# Nucleo.net
KiCad netlist of a schematic drawn in Altium Designer
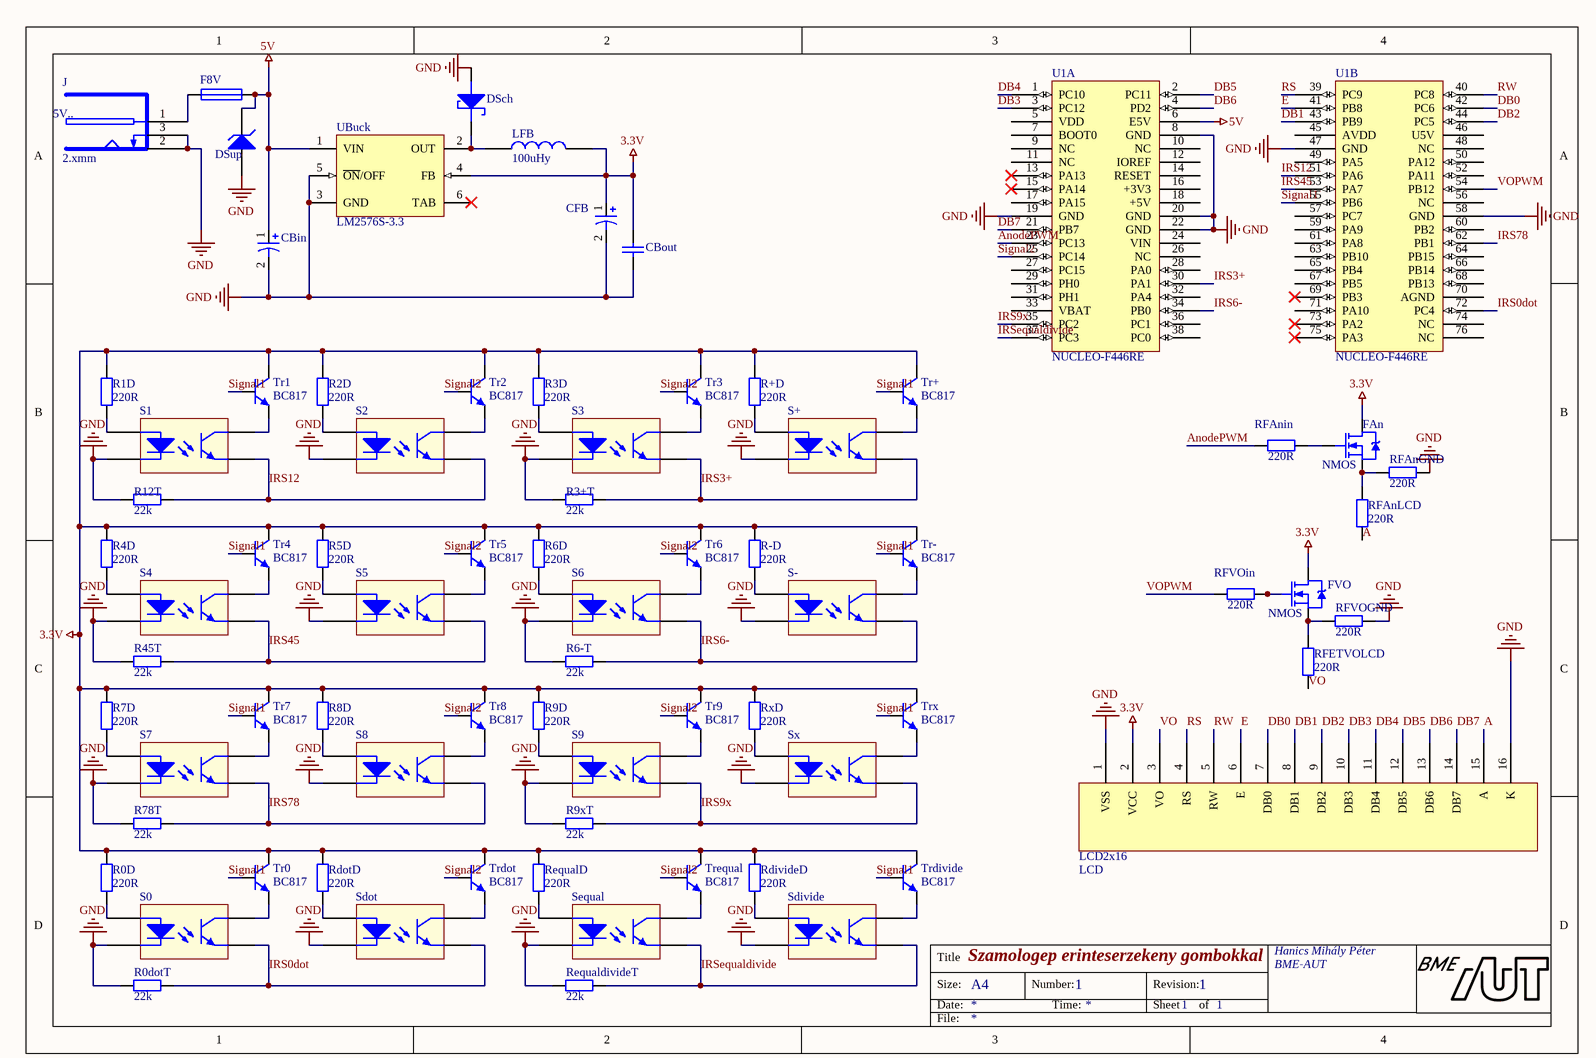
[diagram p0: Nucleo.SchDoc]

(export (version "E")
  (design (tool "Eeschema 10.0.6"))
  (components
    (comp (ref "CBin")
      (value "100uF")
      (footprint "CAP_100uF_ELKO")
      (description "100uF Capacitor")
      (fields (field (name "TOLERANCE") "20%") (field (name "VOLTAGE") "16V"))
      (libsource (lib "hallglib") (part "CAP100uF"))
    )
    (comp (ref "CBout")
      (value "100nF")
      (footprint "FP_0805_CAP_085")
      (description "Capacitor")
      (fields (field (name "TOLERANCE") "10%") (field (name "VOLTAGE") "50V"))
      (libsource (lib "hallglib") (part "CAP"))
    )
    (comp (ref "CFB")
      (value "1000uF")
      (footprint "CAP_Elko1000uF")
      (description "1000uF Capacitor")
      (fields (field (name "TOLERANCE") "20%") (field (name "VOLTAGE") "6.3V"))
      (libsource (lib "hallglib") (part "CAP1000uF"))
    )
    (comp (ref "DSch")
      (value "SCHOTTKY")
      (footprint "FP_SOD323-F")
      (description "Schottky diode")
      (libsource (lib "hallglib") (part "SCHOTTKY"))
    )
    (comp (ref "DSup")
      (value "~")
      (footprint "DiodeSMAJ5A")
      (description "Suppressor Diode")
      (libsource (lib "hallglib") (part "SMAJ5A"))
    )
    (comp (ref "F8V") (value "Fuse") (footprint "FP_MULTIFUSE") (libsource (lib "hallglib") (part "Fuse")))
    (comp (ref "FAn")
      (value "NMOS")
      (footprint "FP_SOT223")
      (description "NXP - BSP030,115 - MOSFET, N CH, 30V, 10A, SOT223")
      (libsource (lib "hallglib") (part "NMOS"))
    )
    (comp (ref "FVO")
      (value "NMOS")
      (footprint "FP_SOT223")
      (description "NXP - BSP030,115 - MOSFET, N CH, 30V, 10A, SOT223")
      (libsource (lib "hallglib") (part "NMOS"))
    )
    (comp (ref "J")
      (value "2.xmm")
      (footprint "FP_DC_TAP_ANYA")
      (description "2.xmm DC HEBA25 TÁPFESZÜLTSÉG ALJZAT ZÁRT, NYÁKBA 90°")
      (libsource (lib "hallglib") (part "DC_TAP_ANYA"))
    )
    (comp (ref "LCD2x16")
      (value "LCD")
      (footprint "FP_LCD2X16curr")
      (description "16x2 LCD")
      (libsource (lib "hallglib") (part "LCD1602"))
    )
    (comp (ref "LFB")
      (value "100uHy")
      (footprint "IND100uHy")
      (description "100uH Inductor")
      (fields (field (name "TOLERANCE") "10%"))
      (libsource (lib "hallglib") (part "IND100uH"))
    )
    (comp (ref "R+D")
      (value "220R")
      (footprint "FP_0805_RES")
      (description "Resistor")
      (fields (field (name "TOLERANCE") "1%") (field (name "POWER") "0.125W"))
      (libsource (lib "hallglib") (part "RES"))
    )
    (comp (ref "R-D")
      (value "220R")
      (footprint "FP_0805_RES")
      (description "Resistor")
      (fields (field (name "TOLERANCE") "1%") (field (name "POWER") "0.125W"))
      (libsource (lib "hallglib") (part "RES"))
    )
    (comp (ref "R0D")
      (value "220R")
      (footprint "FP_0805_RES")
      (description "Resistor")
      (fields (field (name "TOLERANCE") "1%") (field (name "POWER") "0.125W"))
      (libsource (lib "hallglib") (part "RES"))
    )
    (comp (ref "R0dotT")
      (value "22k")
      (footprint "FP_0805_RES")
      (description "Resistor")
      (fields (field (name "TOLERANCE") "1%") (field (name "POWER") "0.125W"))
      (libsource (lib "") (part "RES_2"))
    )
    (comp (ref "R1D")
      (value "220R")
      (footprint "FP_0805_RES")
      (description "Resistor")
      (fields (field (name "TOLERANCE") "1%") (field (name "POWER") "0.125W"))
      (libsource (lib "") (part "RES_3"))
    )
    (comp (ref "R2D")
      (value "220R")
      (footprint "FP_0805_RES")
      (description "Resistor")
      (fields (field (name "TOLERANCE") "1%") (field (name "POWER") "0.125W"))
      (libsource (lib "hallglib") (part "RES"))
    )
    (comp (ref "R3+T")
      (value "22k")
      (footprint "FP_0805_RES")
      (description "Resistor")
      (fields (field (name "TOLERANCE") "1%") (field (name "POWER") "0.125W"))
      (libsource (lib "") (part "RES_1"))
    )
    (comp (ref "R3D")
      (value "220R")
      (footprint "FP_0805_RES")
      (description "Resistor")
      (fields (field (name "TOLERANCE") "1%") (field (name "POWER") "0.125W"))
      (libsource (lib "hallglib") (part "RES"))
    )
    (comp (ref "R4D")
      (value "220R")
      (footprint "FP_0805_RES")
      (description "Resistor")
      (fields (field (name "TOLERANCE") "1%") (field (name "POWER") "0.125W"))
      (libsource (lib "hallglib") (part "RES"))
    )
    (comp (ref "R5D")
      (value "220R")
      (footprint "FP_0805_RES")
      (description "Resistor")
      (fields (field (name "TOLERANCE") "1%") (field (name "POWER") "0.125W"))
      (libsource (lib "hallglib") (part "RES"))
    )
    (comp (ref "R6-T")
      (value "22k")
      (footprint "FP_0805_RES")
      (description "Resistor")
      (fields (field (name "TOLERANCE") "1%") (field (name "POWER") "0.125W"))
      (libsource (lib "") (part "RES_1"))
    )
    (comp (ref "R6D")
      (value "220R")
      (footprint "FP_0805_RES")
      (description "Resistor")
      (fields (field (name "TOLERANCE") "1%") (field (name "POWER") "0.125W"))
      (libsource (lib "hallglib") (part "RES"))
    )
    (comp (ref "R7D")
      (value "220R")
      (footprint "FP_0805_RES")
      (description "Resistor")
      (fields (field (name "TOLERANCE") "1%") (field (name "POWER") "0.125W"))
      (libsource (lib "hallglib") (part "RES"))
    )
    (comp (ref "R8D")
      (value "220R")
      (footprint "FP_0805_RES")
      (description "Resistor")
      (fields (field (name "TOLERANCE") "1%") (field (name "POWER") "0.125W"))
      (libsource (lib "hallglib") (part "RES"))
    )
    (comp (ref "R9D")
      (value "220R")
      (footprint "FP_0805_RES")
      (description "Resistor")
      (fields (field (name "TOLERANCE") "1%") (field (name "POWER") "0.125W"))
      (libsource (lib "hallglib") (part "RES"))
    )
    (comp (ref "R9xT")
      (value "22k")
      (footprint "FP_0805_RES")
      (description "Resistor")
      (fields (field (name "TOLERANCE") "1%") (field (name "POWER") "0.125W"))
      (libsource (lib "") (part "RES_1"))
    )
    (comp (ref "R12T")
      (value "22k")
      (footprint "FP_0805_RES")
      (description "Resistor")
      (fields (field (name "TOLERANCE") "1%") (field (name "POWER") "0.125W"))
      (libsource (lib "") (part "RES_1"))
    )
    (comp (ref "R45T")
      (value "22k")
      (footprint "FP_0805_RES")
      (description "Resistor")
      (fields (field (name "TOLERANCE") "1%") (field (name "POWER") "0.125W"))
      (libsource (lib "") (part "RES_2"))
    )
    (comp (ref "R78T")
      (value "22k")
      (footprint "FP_0805_RES")
      (description "Resistor")
      (fields (field (name "TOLERANCE") "1%") (field (name "POWER") "0.125W"))
      (libsource (lib "") (part "RES_1"))
    )
    (comp (ref "RdivideD")
      (value "220R")
      (footprint "FP_0805_RES")
      (description "Resistor")
      (fields (field (name "TOLERANCE") "1%") (field (name "POWER") "0.125W"))
      (libsource (lib "hallglib") (part "RES"))
    )
    (comp (ref "RdotD")
      (value "220R")
      (footprint "FP_0805_RES")
      (description "Resistor")
      (fields (field (name "TOLERANCE") "1%") (field (name "POWER") "0.125W"))
      (libsource (lib "hallglib") (part "RES"))
    )
    (comp (ref "RequalD")
      (value "220R")
      (footprint "FP_0805_RES")
      (description "Resistor")
      (fields (field (name "TOLERANCE") "1%") (field (name "POWER") "0.125W"))
      (libsource (lib "hallglib") (part "RES"))
    )
    (comp (ref "RequaldivideT")
      (value "22k")
      (footprint "FP_0805_RES")
      (description "Resistor")
      (fields (field (name "TOLERANCE") "1%") (field (name "POWER") "0.125W"))
      (libsource (lib "") (part "RES_1"))
    )
    (comp (ref "RFAnGND")
      (value "220R")
      (footprint "FP_0805_RES")
      (description "Resistor")
      (fields (field (name "TOLERANCE") "1%") (field (name "POWER") "0.125W"))
      (libsource (lib "") (part "RES_1"))
    )
    (comp (ref "RFAnin")
      (value "220R")
      (footprint "FP_0805_RES")
      (description "Resistor")
      (fields (field (name "TOLERANCE") "1%") (field (name "POWER") "0.125W"))
      (libsource (lib "") (part "RES_1"))
    )
    (comp (ref "RFAnLCD")
      (value "220R")
      (footprint "FP_0805_RES")
      (description "Resistor")
      (fields (field (name "TOLERANCE") "1%") (field (name "POWER") "0.125W"))
      (libsource (lib "hallglib") (part "RES"))
    )
    (comp (ref "RFETVOLCD")
      (value "220R")
      (footprint "FP_0805_RES")
      (description "Resistor")
      (fields (field (name "TOLERANCE") "1%") (field (name "POWER") "0.125W"))
      (libsource (lib "hallglib") (part "RES"))
    )
    (comp (ref "RFVOGND")
      (value "220R")
      (footprint "FP_0805_RES")
      (description "Resistor")
      (fields (field (name "TOLERANCE") "1%") (field (name "POWER") "0.125W"))
      (libsource (lib "") (part "RES_1"))
    )
    (comp (ref "RFVOin")
      (value "220R")
      (footprint "FP_0805_RES")
      (description "Resistor")
      (fields (field (name "TOLERANCE") "1%") (field (name "POWER") "0.125W"))
      (libsource (lib "") (part "RES_1"))
    )
    (comp (ref "RxD")
      (value "220R")
      (footprint "FP_0805_RES")
      (description "Resistor")
      (fields (field (name "TOLERANCE") "1%") (field (name "POWER") "0.125W"))
      (libsource (lib "hallglib") (part "RES"))
    )
    (comp (ref "S+")
      (value "CNY70")
      (footprint "CNY70")
      (description "Reflective Optical Sensor")
      (libsource (lib "hallglib") (part "CNY70"))
    )
    (comp (ref "S-")
      (value "CNY70")
      (footprint "CNY70")
      (description "Reflective Optical Sensor")
      (libsource (lib "hallglib") (part "CNY70"))
    )
    (comp (ref "S0")
      (value "CNY70")
      (footprint "CNY70")
      (description "Reflective Optical Sensor")
      (libsource (lib "hallglib") (part "CNY70"))
    )
    (comp (ref "S1")
      (value "CNY70")
      (footprint "CNY70")
      (description "Reflective Optical Sensor")
      (libsource (lib "hallglib") (part "CNY70"))
    )
    (comp (ref "S2")
      (value "CNY70")
      (footprint "CNY70")
      (description "Reflective Optical Sensor")
      (libsource (lib "hallglib") (part "CNY70"))
    )
    (comp (ref "S3")
      (value "CNY70")
      (footprint "CNY70")
      (description "Reflective Optical Sensor")
      (libsource (lib "hallglib") (part "CNY70"))
    )
    (comp (ref "S4")
      (value "CNY70")
      (footprint "CNY70")
      (description "Reflective Optical Sensor")
      (libsource (lib "hallglib") (part "CNY70"))
    )
    (comp (ref "S5")
      (value "CNY70")
      (footprint "CNY70")
      (description "Reflective Optical Sensor")
      (libsource (lib "hallglib") (part "CNY70"))
    )
    (comp (ref "S6")
      (value "CNY70")
      (footprint "CNY70")
      (description "Reflective Optical Sensor")
      (libsource (lib "hallglib") (part "CNY70"))
    )
    (comp (ref "S7")
      (value "CNY70")
      (footprint "CNY70")
      (description "Reflective Optical Sensor")
      (libsource (lib "hallglib") (part "CNY70"))
    )
    (comp (ref "S8")
      (value "CNY70")
      (footprint "CNY70")
      (description "Reflective Optical Sensor")
      (libsource (lib "hallglib") (part "CNY70"))
    )
    (comp (ref "S9")
      (value "CNY70")
      (footprint "CNY70")
      (description "Reflective Optical Sensor")
      (libsource (lib "hallglib") (part "CNY70"))
    )
    (comp (ref "Sdivide")
      (value "CNY70")
      (footprint "CNY70")
      (description "Reflective Optical Sensor")
      (libsource (lib "hallglib") (part "CNY70"))
    )
    (comp (ref "Sdot")
      (value "CNY70")
      (footprint "CNY70")
      (description "Reflective Optical Sensor")
      (libsource (lib "hallglib") (part "CNY70"))
    )
    (comp (ref "Sequal")
      (value "CNY70")
      (footprint "CNY70")
      (description "Reflective Optical Sensor")
      (libsource (lib "hallglib") (part "CNY70"))
    )
    (comp (ref "Sx")
      (value "CNY70")
      (footprint "CNY70")
      (description "Reflective Optical Sensor")
      (libsource (lib "hallglib") (part "CNY70"))
    )
    (comp (ref "Tr+")
      (value "BC817")
      (footprint "FP_SOT23-3")
      (description "NPN General-purpose Transistor")
      (libsource (lib "hallglib") (part "BC817"))
    )
    (comp (ref "Tr-")
      (value "BC817")
      (footprint "FP_SOT23-3")
      (description "NPN General-purpose Transistor")
      (libsource (lib "hallglib") (part "BC817"))
    )
    (comp (ref "Tr0")
      (value "BC817")
      (footprint "FP_SOT23-3")
      (description "NPN General-purpose Transistor")
      (libsource (lib "hallglib") (part "BC817"))
    )
    (comp (ref "Tr1")
      (value "BC817")
      (footprint "FP_SOT23-3")
      (description "NPN General-purpose Transistor")
      (libsource (lib "hallglib") (part "BC817"))
    )
    (comp (ref "Tr2")
      (value "BC817")
      (footprint "FP_SOT23-3")
      (description "NPN General-purpose Transistor")
      (libsource (lib "hallglib") (part "BC817"))
    )
    (comp (ref "Tr3")
      (value "BC817")
      (footprint "FP_SOT23-3")
      (description "NPN General-purpose Transistor")
      (libsource (lib "hallglib") (part "BC817"))
    )
    (comp (ref "Tr4")
      (value "BC817")
      (footprint "FP_SOT23-3")
      (description "NPN General-purpose Transistor")
      (libsource (lib "hallglib") (part "BC817"))
    )
    (comp (ref "Tr5")
      (value "BC817")
      (footprint "FP_SOT23-3")
      (description "NPN General-purpose Transistor")
      (libsource (lib "hallglib") (part "BC817"))
    )
    (comp (ref "Tr6")
      (value "BC817")
      (footprint "FP_SOT23-3")
      (description "NPN General-purpose Transistor")
      (libsource (lib "hallglib") (part "BC817"))
    )
    (comp (ref "Tr7")
      (value "BC817")
      (footprint "FP_SOT23-3")
      (description "NPN General-purpose Transistor")
      (libsource (lib "hallglib") (part "BC817"))
    )
    (comp (ref "Tr8")
      (value "BC817")
      (footprint "FP_SOT23-3")
      (description "NPN General-purpose Transistor")
      (libsource (lib "hallglib") (part "BC817"))
    )
    (comp (ref "Tr9")
      (value "BC817")
      (footprint "FP_SOT23-3")
      (description "NPN General-purpose Transistor")
      (libsource (lib "hallglib") (part "BC817"))
    )
    (comp (ref "Trdivide")
      (value "BC817")
      (footprint "FP_SOT23-3")
      (description "NPN General-purpose Transistor")
      (libsource (lib "hallglib") (part "BC817"))
    )
    (comp (ref "Trdot")
      (value "BC817")
      (footprint "FP_SOT23-3")
      (description "NPN General-purpose Transistor")
      (libsource (lib "hallglib") (part "BC817"))
    )
    (comp (ref "Trequal")
      (value "BC817")
      (footprint "FP_SOT23-3")
      (description "NPN General-purpose Transistor")
      (libsource (lib "hallglib") (part "BC817"))
    )
    (comp (ref "Trx")
      (value "BC817")
      (footprint "FP_SOT23-3")
      (description "NPN General-purpose Transistor")
      (libsource (lib "hallglib") (part "BC817"))
    )
    (comp (ref "U1")
      (value "NUCLEO-F446RE")
      (footprint "FP_NUCLEO-64")
      (libsource (lib "hallglib") (part "NUCLEO-F446RE"))
    )
    (comp (ref "UBuck")
      (value "LM2576S-3.3")
      (footprint "TS5B_M")
      (description "SIMPLE SWITCHER® 3A Step-Down Voltage Regulator, 5-pin TO-263")
      (fields (field (name "MANUFACTURER") "National Semiconductor"))
      (libsource (lib "Altium Content Vault") (part "PM-REG-LM2575HVS-12"))
    )
  )
  (nets
    (net (code "1") (name "/A") (class "Default")
      (node (ref "LCD2x16") (pin "15") (pinfunction "A_15") (pintype "passive"))
      (node (ref "RFAnLCD") (pin "2") (pinfunction "2_2") (pintype "passive"))
    )
    (net (code "2") (name "/AnodePWM") (class "Default")
      (node (ref "RFAnin") (pin "2") (pinfunction "2_2") (pintype "passive"))
      (node (ref "U1") (pin "23") (pinfunction "PC13_23") (pintype "bidirectional"))
    )
    (net (code "3") (name "/DB0") (class "Default")
      (node (ref "LCD2x16") (pin "7") (pinfunction "DB0_7") (pintype "passive"))
      (node (ref "U1") (pin "42") (pinfunction "PC6_42") (pintype "bidirectional"))
    )
    (net (code "4") (name "/DB1") (class "Default")
      (node (ref "LCD2x16") (pin "8") (pinfunction "DB1_8") (pintype "passive"))
      (node (ref "U1") (pin "43") (pinfunction "PB9_43") (pintype "bidirectional"))
    )
    (net (code "5") (name "/DB2") (class "Default")
      (node (ref "LCD2x16") (pin "9") (pinfunction "DB2_9") (pintype "passive"))
      (node (ref "U1") (pin "44") (pinfunction "PC5_44") (pintype "bidirectional"))
    )
    (net (code "6") (name "/DB3") (class "Default")
      (node (ref "LCD2x16") (pin "10") (pinfunction "DB3_10") (pintype "passive"))
      (node (ref "U1") (pin "3") (pinfunction "PC12_3") (pintype "bidirectional"))
    )
    (net (code "7") (name "/DB4") (class "Default")
      (node (ref "LCD2x16") (pin "11") (pinfunction "DB4_11") (pintype "passive"))
      (node (ref "U1") (pin "1") (pinfunction "PC10_1") (pintype "bidirectional"))
    )
    (net (code "8") (name "/DB5") (class "Default")
      (node (ref "LCD2x16") (pin "12") (pinfunction "DB5_12") (pintype "passive"))
      (node (ref "U1") (pin "2") (pinfunction "PC11_2") (pintype "bidirectional"))
    )
    (net (code "9") (name "/DB6") (class "Default")
      (node (ref "LCD2x16") (pin "13") (pinfunction "DB6_13") (pintype "passive"))
      (node (ref "U1") (pin "4") (pinfunction "PD2_4") (pintype "bidirectional"))
    )
    (net (code "10") (name "/DB7") (class "Default")
      (node (ref "LCD2x16") (pin "14") (pinfunction "DB7_14") (pintype "passive"))
      (node (ref "U1") (pin "21") (pinfunction "PB7_21") (pintype "bidirectional"))
    )
    (net (code "11") (name "/E") (class "Default")
      (node (ref "LCD2x16") (pin "6") (pinfunction "E_6") (pintype "passive"))
      (node (ref "U1") (pin "41") (pinfunction "PB8_41") (pintype "bidirectional"))
    )
    (net (code "12") (name "/IRS0dot") (class "Default")
      (node (ref "R0dotT") (pin "2") (pinfunction "2_2") (pintype "passive"))
      (node (ref "S0") (pin "4") (pinfunction "E_4") (pintype "passive"))
      (node (ref "Sdot") (pin "4") (pinfunction "E_4") (pintype "passive"))
      (node (ref "U1") (pin "72") (pinfunction "PC4_72") (pintype "bidirectional"))
    )
    (net (code "13") (name "/IRS3+") (class "Default")
      (node (ref "R3+T") (pin "1") (pinfunction "1_1") (pintype "passive"))
      (node (ref "S+") (pin "4") (pinfunction "E_4") (pintype "passive"))
      (node (ref "S3") (pin "4") (pinfunction "E_4") (pintype "passive"))
      (node (ref "U1") (pin "30") (pinfunction "PA1_30") (pintype "bidirectional"))
    )
    (net (code "14") (name "/IRS6-") (class "Default")
      (node (ref "R6-T") (pin "1") (pinfunction "1_1") (pintype "passive"))
      (node (ref "S-") (pin "4") (pinfunction "E_4") (pintype "passive"))
      (node (ref "S6") (pin "4") (pinfunction "E_4") (pintype "passive"))
      (node (ref "U1") (pin "34") (pinfunction "PB0_34") (pintype "bidirectional"))
    )
    (net (code "15") (name "/IRS9x") (class "Default")
      (node (ref "R9xT") (pin "1") (pinfunction "1_1") (pintype "passive"))
      (node (ref "S9") (pin "4") (pinfunction "E_4") (pintype "passive"))
      (node (ref "Sx") (pin "4") (pinfunction "E_4") (pintype "passive"))
      (node (ref "U1") (pin "35") (pinfunction "PC2_35") (pintype "bidirectional"))
    )
    (net (code "16") (name "/IRS12") (class "Default")
      (node (ref "R12T") (pin "1") (pinfunction "1_1") (pintype "passive"))
      (node (ref "S1") (pin "4") (pinfunction "E_4") (pintype "passive"))
      (node (ref "S2") (pin "4") (pinfunction "E_4") (pintype "passive"))
      (node (ref "U1") (pin "51") (pinfunction "PA6_51") (pintype "bidirectional"))
    )
    (net (code "17") (name "/IRS45") (class "Default")
      (node (ref "R45T") (pin "2") (pinfunction "2_2") (pintype "passive"))
      (node (ref "S4") (pin "4") (pinfunction "E_4") (pintype "passive"))
      (node (ref "S5") (pin "4") (pinfunction "E_4") (pintype "passive"))
      (node (ref "U1") (pin "53") (pinfunction "PA7_53") (pintype "bidirectional"))
    )
    (net (code "18") (name "/IRS78") (class "Default")
      (node (ref "R78T") (pin "1") (pinfunction "1_1") (pintype "passive"))
      (node (ref "S7") (pin "4") (pinfunction "E_4") (pintype "passive"))
      (node (ref "S8") (pin "4") (pinfunction "E_4") (pintype "passive"))
      (node (ref "U1") (pin "62") (pinfunction "PB1_62") (pintype "bidirectional"))
    )
    (net (code "19") (name "/IRSequaldivide") (class "Default")
      (node (ref "RequaldivideT") (pin "1") (pinfunction "1_1") (pintype "passive"))
      (node (ref "Sdivide") (pin "4") (pinfunction "E_4") (pintype "passive"))
      (node (ref "Sequal") (pin "4") (pinfunction "E_4") (pintype "passive"))
      (node (ref "U1") (pin "37") (pinfunction "PC3_37") (pintype "bidirectional"))
    )
    (net (code "20") (name "/RS") (class "Default")
      (node (ref "LCD2x16") (pin "4") (pinfunction "RS_4") (pintype "passive"))
      (node (ref "U1") (pin "39") (pinfunction "PC9_39") (pintype "bidirectional"))
    )
    (net (code "21") (name "/RW") (class "Default")
      (node (ref "LCD2x16") (pin "5") (pinfunction "RW_5") (pintype "passive"))
      (node (ref "U1") (pin "40") (pinfunction "PC8_40") (pintype "bidirectional"))
    )
    (net (code "22") (name "/Signal1") (class "Default")
      (node (ref "Tr+") (pin "1") (pinfunction "B_1") (pintype "passive"))
      (node (ref "Tr-") (pin "1") (pinfunction "B_1") (pintype "passive"))
      (node (ref "Tr0") (pin "1") (pinfunction "B_1") (pintype "passive"))
      (node (ref "Tr1") (pin "1") (pinfunction "B_1") (pintype "passive"))
      (node (ref "Tr4") (pin "1") (pinfunction "B_1") (pintype "passive"))
      (node (ref "Tr7") (pin "1") (pinfunction "B_1") (pintype "passive"))
      (node (ref "Trdivide") (pin "1") (pinfunction "B_1") (pintype "passive"))
      (node (ref "Trx") (pin "1") (pinfunction "B_1") (pintype "passive"))
      (node (ref "U1") (pin "55") (pinfunction "PB6_55") (pintype "bidirectional"))
    )
    (net (code "23") (name "/Signal2") (class "Default")
      (node (ref "Tr2") (pin "1") (pinfunction "B_1") (pintype "passive"))
      (node (ref "Tr3") (pin "1") (pinfunction "B_1") (pintype "passive"))
      (node (ref "Tr5") (pin "1") (pinfunction "B_1") (pintype "passive"))
      (node (ref "Tr6") (pin "1") (pinfunction "B_1") (pintype "passive"))
      (node (ref "Tr8") (pin "1") (pinfunction "B_1") (pintype "passive"))
      (node (ref "Tr9") (pin "1") (pinfunction "B_1") (pintype "passive"))
      (node (ref "Trdot") (pin "1") (pinfunction "B_1") (pintype "passive"))
      (node (ref "Trequal") (pin "1") (pinfunction "B_1") (pintype "passive"))
      (node (ref "U1") (pin "25") (pinfunction "PC14_25") (pintype "bidirectional"))
    )
    (net (code "24") (name "/VO") (class "Default")
      (node (ref "LCD2x16") (pin "3") (pinfunction "VO_3") (pintype "passive"))
      (node (ref "RFETVOLCD") (pin "2") (pinfunction "2_2") (pintype "passive"))
    )
    (net (code "25") (name "/VOPWM") (class "Default")
      (node (ref "RFVOin") (pin "2") (pinfunction "2_2") (pintype "passive"))
      (node (ref "U1") (pin "54") (pinfunction "PB12_54") (pintype "bidirectional"))
    )
    (net (code "26") (name "3.3V") (class "Default")
      (node (ref "CBout") (pin "2") (pinfunction "2_2") (pintype "passive"))
      (node (ref "CFB") (pin "1") (pinfunction "1_1") (pintype "passive"))
      (node (ref "FAn") (pin "2") (pinfunction "D_2") (pintype "passive"))
      (node (ref "FVO") (pin "2") (pinfunction "D_2") (pintype "passive"))
      (node (ref "LCD2x16") (pin "2") (pinfunction "VCC_2") (pintype "passive"))
      (node (ref "LFB") (pin "2") (pinfunction "2_2") (pintype "passive"))
      (node (ref "R+D") (pin "1") (pinfunction "1_1") (pintype "passive"))
      (node (ref "R-D") (pin "1") (pinfunction "1_1") (pintype "passive"))
      (node (ref "R0D") (pin "1") (pinfunction "1_1") (pintype "passive"))
      (node (ref "R1D") (pin "2") (pinfunction "2_2") (pintype "passive"))
      (node (ref "R2D") (pin "1") (pinfunction "1_1") (pintype "passive"))
      (node (ref "R3D") (pin "1") (pinfunction "1_1") (pintype "passive"))
      (node (ref "R4D") (pin "1") (pinfunction "1_1") (pintype "passive"))
      (node (ref "R5D") (pin "1") (pinfunction "1_1") (pintype "passive"))
      (node (ref "R6D") (pin "1") (pinfunction "1_1") (pintype "passive"))
      (node (ref "R7D") (pin "1") (pinfunction "1_1") (pintype "passive"))
      (node (ref "R8D") (pin "1") (pinfunction "1_1") (pintype "passive"))
      (node (ref "R9D") (pin "1") (pinfunction "1_1") (pintype "passive"))
      (node (ref "RdivideD") (pin "1") (pinfunction "1_1") (pintype "passive"))
      (node (ref "RdotD") (pin "1") (pinfunction "1_1") (pintype "passive"))
      (node (ref "RequalD") (pin "1") (pinfunction "1_1") (pintype "passive"))
      (node (ref "RxD") (pin "1") (pinfunction "1_1") (pintype "passive"))
      (node (ref "Tr+") (pin "3") (pinfunction "C_3") (pintype "passive"))
      (node (ref "Tr-") (pin "3") (pinfunction "C_3") (pintype "passive"))
      (node (ref "Tr0") (pin "3") (pinfunction "C_3") (pintype "passive"))
      (node (ref "Tr1") (pin "3") (pinfunction "C_3") (pintype "passive"))
      (node (ref "Tr2") (pin "3") (pinfunction "C_3") (pintype "passive"))
      (node (ref "Tr3") (pin "3") (pinfunction "C_3") (pintype "passive"))
      (node (ref "Tr4") (pin "3") (pinfunction "C_3") (pintype "passive"))
      (node (ref "Tr5") (pin "3") (pinfunction "C_3") (pintype "passive"))
      (node (ref "Tr6") (pin "3") (pinfunction "C_3") (pintype "passive"))
      (node (ref "Tr7") (pin "3") (pinfunction "C_3") (pintype "passive"))
      (node (ref "Tr8") (pin "3") (pinfunction "C_3") (pintype "passive"))
      (node (ref "Tr9") (pin "3") (pinfunction "C_3") (pintype "passive"))
      (node (ref "Trdivide") (pin "3") (pinfunction "C_3") (pintype "passive"))
      (node (ref "Trdot") (pin "3") (pinfunction "C_3") (pintype "passive"))
      (node (ref "Trequal") (pin "3") (pinfunction "C_3") (pintype "passive"))
      (node (ref "Trx") (pin "3") (pinfunction "C_3") (pintype "passive"))
      (node (ref "UBuck") (pin "4") (pinfunction "FB_4") (pintype "input"))
    )
    (net (code "27") (name "5V") (class "Default")
      (node (ref "CBin") (pin "1") (pinfunction "1_1") (pintype "passive"))
      (node (ref "DSup") (pin "1") (pinfunction "K_1") (pintype "passive"))
      (node (ref "F8V") (pin "2") (pinfunction "2_2") (pintype "passive"))
      (node (ref "U1") (pin "6") (pinfunction "E5V_6") (pintype "power_in"))
      (node (ref "UBuck") (pin "1") (pinfunction "VIN_1") (pintype "power_in"))
    )
    (net (code "28") (name "GND") (class "Default")
      (node (ref "CBin") (pin "2") (pinfunction "2_2") (pintype "passive"))
      (node (ref "CBout") (pin "1") (pinfunction "1_1") (pintype "passive"))
      (node (ref "CFB") (pin "2") (pinfunction "2_2") (pintype "passive"))
      (node (ref "DSch") (pin "1") (pinfunction "ANODE_1") (pintype "passive"))
      (node (ref "DSup") (pin "2") (pinfunction "A_2") (pintype "passive"))
      (node (ref "J") (pin "2") (pinfunction "SLEEVE_2") (pintype "power_in"))
      (node (ref "J") (pin "3") (pinfunction "BREAK_3") (pintype "power_in"))
      (node (ref "LCD2x16") (pin "1") (pinfunction "VSS_1") (pintype "passive"))
      (node (ref "LCD2x16") (pin "16") (pinfunction "K_16") (pintype "passive"))
      (node (ref "R0dotT") (pin "1") (pinfunction "1_1") (pintype "passive"))
      (node (ref "R12T") (pin "2") (pinfunction "2_2") (pintype "passive"))
      (node (ref "R3+T") (pin "2") (pinfunction "2_2") (pintype "passive"))
      (node (ref "R45T") (pin "1") (pinfunction "1_1") (pintype "passive"))
      (node (ref "R6-T") (pin "2") (pinfunction "2_2") (pintype "passive"))
      (node (ref "R78T") (pin "2") (pinfunction "2_2") (pintype "passive"))
      (node (ref "R9xT") (pin "2") (pinfunction "2_2") (pintype "passive"))
      (node (ref "RFAnGND") (pin "1") (pinfunction "1_1") (pintype "passive"))
      (node (ref "RFVOGND") (pin "1") (pinfunction "1_1") (pintype "passive"))
      (node (ref "RequaldivideT") (pin "2") (pinfunction "2_2") (pintype "passive"))
      (node (ref "S+") (pin "2") (pinfunction "K_2") (pintype "passive"))
      (node (ref "S-") (pin "2") (pinfunction "K_2") (pintype "passive"))
      (node (ref "S0") (pin "2") (pinfunction "K_2") (pintype "passive"))
      (node (ref "S1") (pin "2") (pinfunction "K_2") (pintype "passive"))
      (node (ref "S2") (pin "2") (pinfunction "K_2") (pintype "passive"))
      (node (ref "S3") (pin "2") (pinfunction "K_2") (pintype "passive"))
      (node (ref "S4") (pin "2") (pinfunction "K_2") (pintype "passive"))
      (node (ref "S5") (pin "2") (pinfunction "K_2") (pintype "passive"))
      (node (ref "S6") (pin "2") (pinfunction "K_2") (pintype "passive"))
      (node (ref "S7") (pin "2") (pinfunction "K_2") (pintype "passive"))
      (node (ref "S8") (pin "2") (pinfunction "K_2") (pintype "passive"))
      (node (ref "S9") (pin "2") (pinfunction "K_2") (pintype "passive"))
      (node (ref "Sdivide") (pin "2") (pinfunction "K_2") (pintype "passive"))
      (node (ref "Sdot") (pin "2") (pinfunction "K_2") (pintype "passive"))
      (node (ref "Sequal") (pin "2") (pinfunction "K_2") (pintype "passive"))
      (node (ref "Sx") (pin "2") (pinfunction "K_2") (pintype "passive"))
      (node (ref "U1") (pin "19") (pinfunction "GND_19") (pintype "passive"))
      (node (ref "U1") (pin "20") (pinfunction "GND_20") (pintype "passive"))
      (node (ref "U1") (pin "22") (pinfunction "GND_22") (pintype "passive"))
      (node (ref "U1") (pin "47") (pinfunction "GND_47") (pintype "passive"))
      (node (ref "U1") (pin "58") (pinfunction "GND_58") (pintype "passive"))
      (node (ref "U1") (pin "8") (pinfunction "GND_8") (pintype "passive"))
      (node (ref "UBuck") (pin "3") (pinfunction "GND_3") (pintype "power_in"))
      (node (ref "UBuck") (pin "5") (pinfunction "~{ON}/OFF_5") (pintype "input"))
    )
    (net (code "29") (name "Net-(DSch-CATHODE)") (class "Default")
      (node (ref "DSch") (pin "2") (pinfunction "CATHODE_2") (pintype "passive"))
      (node (ref "LFB") (pin "1") (pinfunction "1_1") (pintype "passive"))
      (node (ref "UBuck") (pin "2") (pinfunction "OUT_2") (pintype "power_in"))
    )
    (net (code "30") (name "Net-(FAn-G)") (class "Default")
      (node (ref "FAn") (pin "1") (pinfunction "G_1") (pintype "passive"))
      (node (ref "RFAnin") (pin "1") (pinfunction "1_1") (pintype "passive"))
    )
    (net (code "31") (name "Net-(FAn-S)") (class "Default")
      (node (ref "FAn") (pin "3") (pinfunction "S_3") (pintype "passive"))
      (node (ref "RFAnGND") (pin "2") (pinfunction "2_2") (pintype "passive"))
      (node (ref "RFAnLCD") (pin "1") (pinfunction "1_1") (pintype "passive"))
    )
    (net (code "32") (name "Net-(FVO-G)") (class "Default")
      (node (ref "FVO") (pin "1") (pinfunction "G_1") (pintype "passive"))
      (node (ref "RFVOin") (pin "1") (pinfunction "1_1") (pintype "passive"))
    )
    (net (code "33") (name "Net-(FVO-S)") (class "Default")
      (node (ref "FVO") (pin "3") (pinfunction "S_3") (pintype "passive"))
      (node (ref "RFETVOLCD") (pin "1") (pinfunction "1_1") (pintype "passive"))
      (node (ref "RFVOGND") (pin "2") (pinfunction "2_2") (pintype "passive"))
    )
    (net (code "34") (name "Net-(J-PIN)") (class "Default")
      (node (ref "F8V") (pin "1") (pinfunction "1_1") (pintype "passive"))
      (node (ref "J") (pin "1") (pinfunction "PIN_1") (pintype "power_in"))
    )
    (net (code "35") (name "Net-(S+-A)") (class "Default")
      (node (ref "R+D") (pin "2") (pinfunction "2_2") (pintype "passive"))
      (node (ref "S+") (pin "1") (pinfunction "A_1") (pintype "passive"))
    )
    (net (code "36") (name "Net-(S+-C)") (class "Default")
      (node (ref "S+") (pin "3") (pinfunction "C_3") (pintype "passive"))
      (node (ref "Tr+") (pin "2") (pinfunction "E_2") (pintype "passive"))
    )
    (net (code "37") (name "Net-(S--A)") (class "Default")
      (node (ref "R-D") (pin "2") (pinfunction "2_2") (pintype "passive"))
      (node (ref "S-") (pin "1") (pinfunction "A_1") (pintype "passive"))
    )
    (net (code "38") (name "Net-(S--C)") (class "Default")
      (node (ref "S-") (pin "3") (pinfunction "C_3") (pintype "passive"))
      (node (ref "Tr-") (pin "2") (pinfunction "E_2") (pintype "passive"))
    )
    (net (code "39") (name "Net-(S0-A)") (class "Default")
      (node (ref "R0D") (pin "2") (pinfunction "2_2") (pintype "passive"))
      (node (ref "S0") (pin "1") (pinfunction "A_1") (pintype "passive"))
    )
    (net (code "40") (name "Net-(S0-C)") (class "Default")
      (node (ref "S0") (pin "3") (pinfunction "C_3") (pintype "passive"))
      (node (ref "Tr0") (pin "2") (pinfunction "E_2") (pintype "passive"))
    )
    (net (code "41") (name "Net-(S1-A)") (class "Default")
      (node (ref "R1D") (pin "1") (pinfunction "1_1") (pintype "passive"))
      (node (ref "S1") (pin "1") (pinfunction "A_1") (pintype "passive"))
    )
    (net (code "42") (name "Net-(S1-C)") (class "Default")
      (node (ref "S1") (pin "3") (pinfunction "C_3") (pintype "passive"))
      (node (ref "Tr1") (pin "2") (pinfunction "E_2") (pintype "passive"))
    )
    (net (code "43") (name "Net-(S2-A)") (class "Default")
      (node (ref "R2D") (pin "2") (pinfunction "2_2") (pintype "passive"))
      (node (ref "S2") (pin "1") (pinfunction "A_1") (pintype "passive"))
    )
    (net (code "44") (name "Net-(S2-C)") (class "Default")
      (node (ref "S2") (pin "3") (pinfunction "C_3") (pintype "passive"))
      (node (ref "Tr2") (pin "2") (pinfunction "E_2") (pintype "passive"))
    )
    (net (code "45") (name "Net-(S3-A)") (class "Default")
      (node (ref "R3D") (pin "2") (pinfunction "2_2") (pintype "passive"))
      (node (ref "S3") (pin "1") (pinfunction "A_1") (pintype "passive"))
    )
    (net (code "46") (name "Net-(S3-C)") (class "Default")
      (node (ref "S3") (pin "3") (pinfunction "C_3") (pintype "passive"))
      (node (ref "Tr3") (pin "2") (pinfunction "E_2") (pintype "passive"))
    )
    (net (code "47") (name "Net-(S4-A)") (class "Default")
      (node (ref "R4D") (pin "2") (pinfunction "2_2") (pintype "passive"))
      (node (ref "S4") (pin "1") (pinfunction "A_1") (pintype "passive"))
    )
    (net (code "48") (name "Net-(S4-C)") (class "Default")
      (node (ref "S4") (pin "3") (pinfunction "C_3") (pintype "passive"))
      (node (ref "Tr4") (pin "2") (pinfunction "E_2") (pintype "passive"))
    )
    (net (code "49") (name "Net-(S5-A)") (class "Default")
      (node (ref "R5D") (pin "2") (pinfunction "2_2") (pintype "passive"))
      (node (ref "S5") (pin "1") (pinfunction "A_1") (pintype "passive"))
    )
    (net (code "50") (name "Net-(S5-C)") (class "Default")
      (node (ref "S5") (pin "3") (pinfunction "C_3") (pintype "passive"))
      (node (ref "Tr5") (pin "2") (pinfunction "E_2") (pintype "passive"))
    )
    (net (code "51") (name "Net-(S6-A)") (class "Default")
      (node (ref "R6D") (pin "2") (pinfunction "2_2") (pintype "passive"))
      (node (ref "S6") (pin "1") (pinfunction "A_1") (pintype "passive"))
    )
    (net (code "52") (name "Net-(S6-C)") (class "Default")
      (node (ref "S6") (pin "3") (pinfunction "C_3") (pintype "passive"))
      (node (ref "Tr6") (pin "2") (pinfunction "E_2") (pintype "passive"))
    )
    (net (code "53") (name "Net-(S7-A)") (class "Default")
      (node (ref "R7D") (pin "2") (pinfunction "2_2") (pintype "passive"))
      (node (ref "S7") (pin "1") (pinfunction "A_1") (pintype "passive"))
    )
    (net (code "54") (name "Net-(S7-C)") (class "Default")
      (node (ref "S7") (pin "3") (pinfunction "C_3") (pintype "passive"))
      (node (ref "Tr7") (pin "2") (pinfunction "E_2") (pintype "passive"))
    )
    (net (code "55") (name "Net-(S8-A)") (class "Default")
      (node (ref "R8D") (pin "2") (pinfunction "2_2") (pintype "passive"))
      (node (ref "S8") (pin "1") (pinfunction "A_1") (pintype "passive"))
    )
    (net (code "56") (name "Net-(S8-C)") (class "Default")
      (node (ref "S8") (pin "3") (pinfunction "C_3") (pintype "passive"))
      (node (ref "Tr8") (pin "2") (pinfunction "E_2") (pintype "passive"))
    )
    (net (code "57") (name "Net-(S9-A)") (class "Default")
      (node (ref "R9D") (pin "2") (pinfunction "2_2") (pintype "passive"))
      (node (ref "S9") (pin "1") (pinfunction "A_1") (pintype "passive"))
    )
    (net (code "58") (name "Net-(S9-C)") (class "Default")
      (node (ref "S9") (pin "3") (pinfunction "C_3") (pintype "passive"))
      (node (ref "Tr9") (pin "2") (pinfunction "E_2") (pintype "passive"))
    )
    (net (code "59") (name "Net-(Sdivide-A)") (class "Default")
      (node (ref "RdivideD") (pin "2") (pinfunction "2_2") (pintype "passive"))
      (node (ref "Sdivide") (pin "1") (pinfunction "A_1") (pintype "passive"))
    )
    (net (code "60") (name "Net-(Sdivide-C)") (class "Default")
      (node (ref "Sdivide") (pin "3") (pinfunction "C_3") (pintype "passive"))
      (node (ref "Trdivide") (pin "2") (pinfunction "E_2") (pintype "passive"))
    )
    (net (code "61") (name "Net-(Sdot-A)") (class "Default")
      (node (ref "RdotD") (pin "2") (pinfunction "2_2") (pintype "passive"))
      (node (ref "Sdot") (pin "1") (pinfunction "A_1") (pintype "passive"))
    )
    (net (code "62") (name "Net-(Sdot-C)") (class "Default")
      (node (ref "Sdot") (pin "3") (pinfunction "C_3") (pintype "passive"))
      (node (ref "Trdot") (pin "2") (pinfunction "E_2") (pintype "passive"))
    )
    (net (code "63") (name "Net-(Sequal-A)") (class "Default")
      (node (ref "RequalD") (pin "2") (pinfunction "2_2") (pintype "passive"))
      (node (ref "Sequal") (pin "1") (pinfunction "A_1") (pintype "passive"))
    )
    (net (code "64") (name "Net-(Sequal-C)") (class "Default")
      (node (ref "Sequal") (pin "3") (pinfunction "C_3") (pintype "passive"))
      (node (ref "Trequal") (pin "2") (pinfunction "E_2") (pintype "passive"))
    )
    (net (code "65") (name "Net-(Sx-A)") (class "Default")
      (node (ref "RxD") (pin "2") (pinfunction "2_2") (pintype "passive"))
      (node (ref "Sx") (pin "1") (pinfunction "A_1") (pintype "passive"))
    )
    (net (code "66") (name "Net-(Sx-C)") (class "Default")
      (node (ref "Sx") (pin "3") (pinfunction "C_3") (pintype "passive"))
      (node (ref "Trx") (pin "2") (pinfunction "E_2") (pintype "passive"))
    )
    (net (code "67") (name "unconnected-(U1A-+3V3-Pad16)") (class "Default")
      (node (ref "U1") (pin "16") (pinfunction "+3V3_16") (pintype "power_in"))
    )
    (net (code "68") (name "unconnected-(U1A-+5V-Pad18)") (class "Default")
      (node (ref "U1") (pin "18") (pinfunction "+5V_18") (pintype "power_in"))
    )
    (net (code "69") (name "unconnected-(U1A-BOOT0-Pad7)") (class "Default")
      (node (ref "U1") (pin "7") (pinfunction "BOOT0_7") (pintype "passive"))
    )
    (net (code "70") (name "unconnected-(U1A-IOREF-Pad12)") (class "Default")
      (node (ref "U1") (pin "12") (pinfunction "IOREF_12") (pintype "passive"))
    )
    (net (code "71") (name "unconnected-(U1A-NC-Pad9)") (class "Default")
      (node (ref "U1") (pin "9") (pinfunction "NC_9") (pintype "passive"))
    )
    (net (code "72") (name "unconnected-(U1A-NC-Pad10)") (class "Default")
      (node (ref "U1") (pin "10") (pinfunction "NC_10") (pintype "passive"))
    )
    (net (code "73") (name "unconnected-(U1A-NC-Pad11)") (class "Default")
      (node (ref "U1") (pin "11") (pinfunction "NC_11") (pintype "passive"))
    )
    (net (code "74") (name "unconnected-(U1A-NC-Pad26)") (class "Default")
      (node (ref "U1") (pin "26") (pinfunction "NC_26") (pintype "passive"))
    )
    (net (code "75") (name "unconnected-(U1A-PA0-Pad28)") (class "Default")
      (node (ref "U1") (pin "28") (pinfunction "PA0_28") (pintype "bidirectional"))
    )
    (net (code "76") (name "unconnected-(U1A-PA4-Pad32)") (class "Default")
      (node (ref "U1") (pin "32") (pinfunction "PA4_32") (pintype "bidirectional"))
    )
    (net (code "77") (name "unconnected-(U1A-PA13-Pad13)") (class "Default")
      (node (ref "U1") (pin "13") (pinfunction "PA13_13") (pintype "bidirectional+no_connect"))
    )
    (net (code "78") (name "unconnected-(U1A-PA14-Pad15)") (class "Default")
      (node (ref "U1") (pin "15") (pinfunction "PA14_15") (pintype "bidirectional+no_connect"))
    )
    (net (code "79") (name "unconnected-(U1A-PA15-Pad17)") (class "Default")
      (node (ref "U1") (pin "17") (pinfunction "PA15_17") (pintype "bidirectional"))
    )
    (net (code "80") (name "unconnected-(U1A-PC0-Pad38)") (class "Default")
      (node (ref "U1") (pin "38") (pinfunction "PC0_38") (pintype "bidirectional"))
    )
    (net (code "81") (name "unconnected-(U1A-PC1-Pad36)") (class "Default")
      (node (ref "U1") (pin "36") (pinfunction "PC1_36") (pintype "bidirectional"))
    )
    (net (code "82") (name "unconnected-(U1A-PC15-Pad27)") (class "Default")
      (node (ref "U1") (pin "27") (pinfunction "PC15_27") (pintype "bidirectional"))
    )
    (net (code "83") (name "unconnected-(U1A-PH0-Pad29)") (class "Default")
      (node (ref "U1") (pin "29") (pinfunction "PH0_29") (pintype "bidirectional"))
    )
    (net (code "84") (name "unconnected-(U1A-PH1-Pad31)") (class "Default")
      (node (ref "U1") (pin "31") (pinfunction "PH1_31") (pintype "bidirectional"))
    )
    (net (code "85") (name "unconnected-(U1A-RESET-Pad14)") (class "Default")
      (node (ref "U1") (pin "14") (pinfunction "RESET_14") (pintype "passive"))
    )
    (net (code "86") (name "unconnected-(U1A-VBAT-Pad33)") (class "Default")
      (node (ref "U1") (pin "33") (pinfunction "VBAT_33") (pintype "power_in"))
    )
    (net (code "87") (name "unconnected-(U1A-VDD-Pad5)") (class "Default")
      (node (ref "U1") (pin "5") (pinfunction "VDD_5") (pintype "power_in"))
    )
    (net (code "88") (name "unconnected-(U1A-VIN-Pad24)") (class "Default")
      (node (ref "U1") (pin "24") (pinfunction "VIN_24") (pintype "power_in"))
    )
    (net (code "89") (name "unconnected-(U1B-AGND-Pad70)") (class "Default")
      (node (ref "U1") (pin "70") (pinfunction "AGND_70") (pintype "passive"))
    )
    (net (code "90") (name "unconnected-(U1B-AVDD-Pad45)") (class "Default")
      (node (ref "U1") (pin "45") (pinfunction "AVDD_45") (pintype "power_in"))
    )
    (net (code "91") (name "unconnected-(U1B-NC-Pad48)") (class "Default")
      (node (ref "U1") (pin "48") (pinfunction "NC_48") (pintype "passive"))
    )
    (net (code "92") (name "unconnected-(U1B-NC-Pad56)") (class "Default")
      (node (ref "U1") (pin "56") (pinfunction "NC_56") (pintype "passive"))
    )
    (net (code "93") (name "unconnected-(U1B-NC-Pad74)") (class "Default")
      (node (ref "U1") (pin "74") (pinfunction "NC_74") (pintype "passive"))
    )
    (net (code "94") (name "unconnected-(U1B-NC-Pad76)") (class "Default")
      (node (ref "U1") (pin "76") (pinfunction "NC_76") (pintype "passive"))
    )
    (net (code "95") (name "unconnected-(U1B-PA2-Pad73)") (class "Default")
      (node (ref "U1") (pin "73") (pinfunction "PA2_73") (pintype "bidirectional+no_connect"))
    )
    (net (code "96") (name "unconnected-(U1B-PA3-Pad75)") (class "Default")
      (node (ref "U1") (pin "75") (pinfunction "PA3_75") (pintype "bidirectional+no_connect"))
    )
    (net (code "97") (name "unconnected-(U1B-PA5-Pad49)") (class "Default")
      (node (ref "U1") (pin "49") (pinfunction "PA5_49") (pintype "bidirectional"))
    )
    (net (code "98") (name "unconnected-(U1B-PA8-Pad61)") (class "Default")
      (node (ref "U1") (pin "61") (pinfunction "PA8_61") (pintype "bidirectional"))
    )
    (net (code "99") (name "unconnected-(U1B-PA9-Pad59)") (class "Default")
      (node (ref "U1") (pin "59") (pinfunction "PA9_59") (pintype "bidirectional"))
    )
    (net (code "100") (name "unconnected-(U1B-PA10-Pad71)") (class "Default")
      (node (ref "U1") (pin "71") (pinfunction "PA10_71") (pintype "bidirectional"))
    )
    (net (code "101") (name "unconnected-(U1B-PA11-Pad52)") (class "Default")
      (node (ref "U1") (pin "52") (pinfunction "PA11_52") (pintype "bidirectional"))
    )
    (net (code "102") (name "unconnected-(U1B-PA12-Pad50)") (class "Default")
      (node (ref "U1") (pin "50") (pinfunction "PA12_50") (pintype "bidirectional"))
    )
    (net (code "103") (name "unconnected-(U1B-PB2-Pad60)") (class "Default")
      (node (ref "U1") (pin "60") (pinfunction "PB2_60") (pintype "bidirectional"))
    )
    (net (code "104") (name "unconnected-(U1B-PB3-Pad69)") (class "Default")
      (node (ref "U1") (pin "69") (pinfunction "PB3_69") (pintype "bidirectional+no_connect"))
    )
    (net (code "105") (name "unconnected-(U1B-PB4-Pad65)") (class "Default")
      (node (ref "U1") (pin "65") (pinfunction "PB4_65") (pintype "bidirectional"))
    )
    (net (code "106") (name "unconnected-(U1B-PB5-Pad67)") (class "Default")
      (node (ref "U1") (pin "67") (pinfunction "PB5_67") (pintype "bidirectional"))
    )
    (net (code "107") (name "unconnected-(U1B-PB10-Pad63)") (class "Default")
      (node (ref "U1") (pin "63") (pinfunction "PB10_63") (pintype "bidirectional"))
    )
    (net (code "108") (name "unconnected-(U1B-PB13-Pad68)") (class "Default")
      (node (ref "U1") (pin "68") (pinfunction "PB13_68") (pintype "bidirectional"))
    )
    (net (code "109") (name "unconnected-(U1B-PB14-Pad66)") (class "Default")
      (node (ref "U1") (pin "66") (pinfunction "PB14_66") (pintype "bidirectional"))
    )
    (net (code "110") (name "unconnected-(U1B-PB15-Pad64)") (class "Default")
      (node (ref "U1") (pin "64") (pinfunction "PB15_64") (pintype "bidirectional"))
    )
    (net (code "111") (name "unconnected-(U1B-PC7-Pad57)") (class "Default")
      (node (ref "U1") (pin "57") (pinfunction "PC7_57") (pintype "bidirectional"))
    )
    (net (code "112") (name "unconnected-(U1B-U5V-Pad46)") (class "Default")
      (node (ref "U1") (pin "46") (pinfunction "U5V_46") (pintype "power_in"))
    )
    (net (code "113") (name "unconnected-(UBuck-TAB-Pad6)") (class "Default")
      (node (ref "UBuck") (pin "6") (pinfunction "TAB_6") (pintype "power_in+no_connect"))
    )
  )
)
